# gate.net
KiCad netlist of a schematic drawn in EAGLE
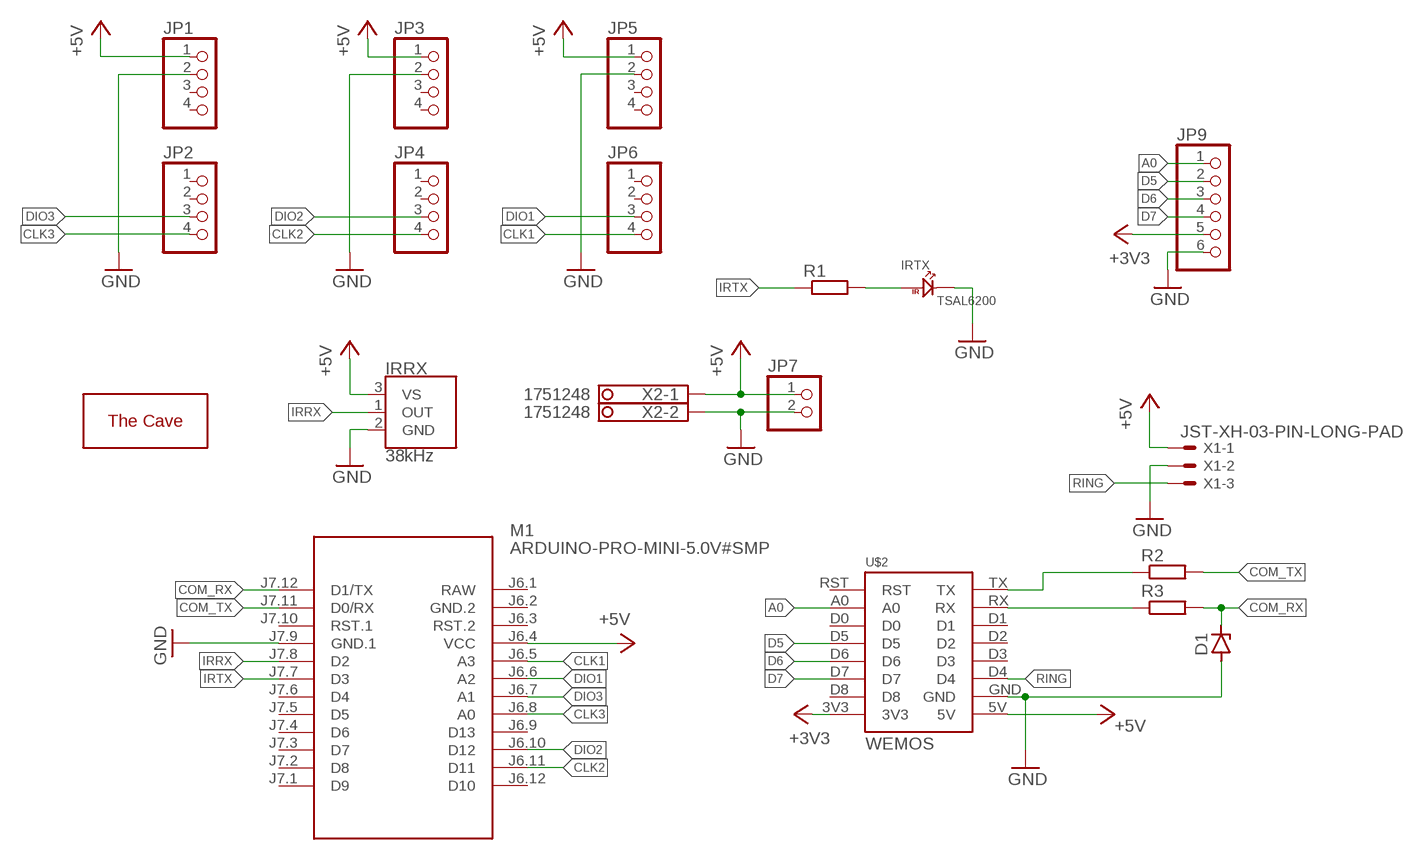
[diagram p0: schematic, sheet 1]

(export (version "E")
  (design (tool "Eeschema 10.0.6"))
  (components
    (comp (ref "D1")
      (value "ZENER-DIODEDO34-7")
      (footprint "eagle-import:DO34Z7")
      (libsource (lib "eagle-import") (part "ZENER-DIODEDO34-7"))
    )
    (comp (ref "IRRX")
      (value "38kHz")
      (footprint "eagle-import:TSOP382")
      (libsource (lib "eagle-import") (part "TSOP38238"))
    )
    (comp (ref "IRTX")
      (value "TSAL6200")
      (footprint "eagle-import:TSAL6200")
      (libsource (lib "eagle-import") (part "TSAL6200"))
    )
    (comp (ref "JP1")
      (value "PINHD-1X4")
      (footprint "eagle-import:1X04")
      (libsource (lib "eagle-import") (part "PINHD-1X4"))
    )
    (comp (ref "JP2")
      (value "PINHD-1X4")
      (footprint "eagle-import:1X04")
      (libsource (lib "eagle-import") (part "PINHD-1X4"))
    )
    (comp (ref "JP3")
      (value "PINHD-1X4")
      (footprint "eagle-import:1X04")
      (libsource (lib "eagle-import") (part "PINHD-1X4"))
    )
    (comp (ref "JP4")
      (value "PINHD-1X4")
      (footprint "eagle-import:1X04")
      (libsource (lib "eagle-import") (part "PINHD-1X4"))
    )
    (comp (ref "JP5")
      (value "PINHD-1X4")
      (footprint "eagle-import:1X04")
      (libsource (lib "eagle-import") (part "PINHD-1X4"))
    )
    (comp (ref "JP6")
      (value "PINHD-1X4")
      (footprint "eagle-import:1X04")
      (libsource (lib "eagle-import") (part "PINHD-1X4"))
    )
    (comp (ref "JP7")
      (value "PINHD-1X2")
      (footprint "eagle-import:1X02")
      (libsource (lib "eagle-import") (part "PINHD-1X2"))
    )
    (comp (ref "JP9")
      (value "PINHD-1X6")
      (footprint "eagle-import:1X06")
      (libsource (lib "eagle-import") (part "PINHD-1X6"))
    )
    (comp (ref "M1")
      (value "ARDUINO-PRO-MINI-5.0V#SMP")
      (footprint "eagle-import:ARDUINO-PRO-MINI#SMP")
      (libsource (lib "eagle-import") (part "ARDUINO-PRO-MINI-#SMP5.0V"))
    )
    (comp (ref "R1")
      (value "R-EU_0207/7")
      (footprint "eagle-import:0207_7")
      (libsource (lib "eagle-import") (part "R-EU_0207/7"))
    )
    (comp (ref "R2")
      (value "R-EU_0207/7")
      (footprint "eagle-import:0207_7")
      (libsource (lib "eagle-import") (part "R-EU_0207/7"))
    )
    (comp (ref "R3")
      (value "R-EU_0207/7")
      (footprint "eagle-import:0207_7")
      (libsource (lib "eagle-import") (part "R-EU_0207/7"))
    )
    (comp (ref "U$2")
      (value "WEMOS")
      (footprint "eagle-import:WEMOS")
      (libsource (lib "eagle-import") (part "WEMOS"))
    )
    (comp (ref "U$3")
      (value "THECAVE_LOGO_NEW_TOP")
      (footprint "eagle-import:NEW_LOGO_TOP")
      (libsource (lib "eagle-import") (part "THECAVE_LOGO_NEW_TOP"))
    )
    (comp (ref "X1")
      (value "JST-XH-03-PIN-LONG-PAD")
      (footprint "eagle-import:JST-XH-03-PACKAGE-LONG-PAD")
      (libsource (lib "eagle-import") (part "JST-XH-03-PIN-LONG-PAD"))
    )
    (comp (ref "X2")
      (value "1751248")
      (footprint "eagle-import:1751248")
      (libsource (lib "eagle-import") (part "1751248"))
    )
  )
  (nets
    (net (code "1") (name "+3V3") (class "Default")
      (node (ref "JP9") (pin "5") (pinfunction "5_5") (pintype "passive"))
      (node (ref "U$2") (pin "3V3") (pinfunction "3V3_3V3") (pintype "bidirectional"))
    )
    (net (code "2") (name "+5V") (class "Default")
      (node (ref "IRRX") (pin "3") (pinfunction "VS_3") (pintype "bidirectional"))
      (node (ref "JP1") (pin "1") (pinfunction "1_1") (pintype "passive"))
      (node (ref "JP3") (pin "1") (pinfunction "1_1") (pintype "passive"))
      (node (ref "JP5") (pin "1") (pinfunction "1_1") (pintype "passive"))
      (node (ref "JP7") (pin "1") (pinfunction "1_1") (pintype "passive"))
      (node (ref "M1") (pin "J6.4") (pinfunction "VCC_J6.4") (pintype "power_in"))
      (node (ref "U$2") (pin "5V") (pinfunction "5V_5V") (pintype "bidirectional"))
      (node (ref "X1") (pin "1") (pinfunction "S_1") (pintype "passive"))
      (node (ref "X2") (pin "1") (pinfunction "K_1") (pintype "passive"))
    )
    (net (code "3") (name "/GND.2") (class "Default")
      (node (ref "M1") (pin "J6.2") (pinfunction "GND.2_J6.2") (pintype "power_in"))
    )
    (net (code "4") (name "/RAW") (class "Default")
      (node (ref "M1") (pin "J6.1") (pinfunction "RAW_J6.1") (pintype "power_in"))
    )
    (net (code "5") (name "A0") (class "Default")
      (node (ref "JP9") (pin "1") (pinfunction "1_1") (pintype "passive"))
      (node (ref "U$2") (pin "A0") (pinfunction "A0_A0") (pintype "bidirectional"))
    )
    (net (code "6") (name "CLK1") (class "Default")
      (node (ref "JP6") (pin "4") (pinfunction "4_4") (pintype "passive"))
      (node (ref "M1") (pin "J6.5") (pinfunction "A3_J6.5") (pintype "bidirectional"))
    )
    (net (code "7") (name "CLK2") (class "Default")
      (node (ref "JP4") (pin "4") (pinfunction "4_4") (pintype "passive"))
      (node (ref "M1") (pin "J6.11") (pinfunction "D11_J6.11") (pintype "bidirectional"))
    )
    (net (code "8") (name "CLK3") (class "Default")
      (node (ref "JP2") (pin "4") (pinfunction "4_4") (pintype "passive"))
      (node (ref "M1") (pin "J6.8") (pinfunction "A0_J6.8") (pintype "bidirectional"))
    )
    (net (code "9") (name "COM_RX") (class "Default")
      (node (ref "D1") (pin "C") (pinfunction "C_C") (pintype "passive"))
      (node (ref "M1") (pin "J7.12") (pinfunction "D1/TX_J7.12") (pintype "bidirectional"))
      (node (ref "R3") (pin "2") (pinfunction "2_2") (pintype "passive"))
    )
    (net (code "10") (name "COM_TX") (class "Default")
      (node (ref "M1") (pin "J7.11") (pinfunction "D0/RX_J7.11") (pintype "bidirectional"))
      (node (ref "R2") (pin "2") (pinfunction "2_2") (pintype "passive"))
    )
    (net (code "11") (name "D5") (class "Default")
      (node (ref "JP9") (pin "2") (pinfunction "2_2") (pintype "passive"))
      (node (ref "U$2") (pin "D5") (pinfunction "D5_D5") (pintype "bidirectional"))
    )
    (net (code "12") (name "D6") (class "Default")
      (node (ref "JP9") (pin "3") (pinfunction "3_3") (pintype "passive"))
      (node (ref "U$2") (pin "D6") (pinfunction "D6_D6") (pintype "bidirectional"))
    )
    (net (code "13") (name "D7") (class "Default")
      (node (ref "JP9") (pin "4") (pinfunction "4_4") (pintype "passive"))
      (node (ref "U$2") (pin "D7") (pinfunction "D7_D7") (pintype "bidirectional"))
    )
    (net (code "14") (name "DIO1") (class "Default")
      (node (ref "JP6") (pin "3") (pinfunction "3_3") (pintype "passive"))
      (node (ref "M1") (pin "J6.6") (pinfunction "A2_J6.6") (pintype "bidirectional"))
    )
    (net (code "15") (name "DIO2") (class "Default")
      (node (ref "JP4") (pin "3") (pinfunction "3_3") (pintype "passive"))
      (node (ref "M1") (pin "J6.10") (pinfunction "D12_J6.10") (pintype "bidirectional"))
    )
    (net (code "16") (name "DIO3") (class "Default")
      (node (ref "JP2") (pin "3") (pinfunction "3_3") (pintype "passive"))
      (node (ref "M1") (pin "J6.7") (pinfunction "A1_J6.7") (pintype "bidirectional"))
    )
    (net (code "17") (name "GND") (class "Default")
      (node (ref "D1") (pin "A") (pinfunction "A_A") (pintype "passive"))
      (node (ref "IRRX") (pin "2") (pinfunction "GND_2") (pintype "bidirectional"))
      (node (ref "IRTX") (pin "N") (pinfunction "N_N") (pintype "bidirectional"))
      (node (ref "JP1") (pin "2") (pinfunction "2_2") (pintype "passive"))
      (node (ref "JP3") (pin "2") (pinfunction "2_2") (pintype "passive"))
      (node (ref "JP5") (pin "2") (pinfunction "2_2") (pintype "passive"))
      (node (ref "JP7") (pin "2") (pinfunction "2_2") (pintype "passive"))
      (node (ref "JP9") (pin "6") (pinfunction "6_6") (pintype "passive"))
      (node (ref "M1") (pin "J7.9") (pinfunction "GND.1_J7.9") (pintype "power_in"))
      (node (ref "U$2") (pin "GND") (pinfunction "GND_GND") (pintype "bidirectional"))
      (node (ref "X1") (pin "2") (pinfunction "S_2") (pintype "passive"))
      (node (ref "X2") (pin "2") (pinfunction "K_2") (pintype "passive"))
    )
    (net (code "18") (name "IRRX") (class "Default")
      (node (ref "IRRX") (pin "1") (pinfunction "OUT_1") (pintype "bidirectional"))
      (node (ref "M1") (pin "J7.8") (pinfunction "D2_J7.8") (pintype "bidirectional"))
    )
    (net (code "19") (name "IRTX") (class "Default")
      (node (ref "M1") (pin "J7.7") (pinfunction "D3_J7.7") (pintype "bidirectional"))
      (node (ref "R1") (pin "1") (pinfunction "1_1") (pintype "passive"))
    )
    (net (code "20") (name "Net-(IRTX-PadP)") (class "Default")
      (node (ref "IRTX") (pin "P") (pinfunction "P_P") (pintype "bidirectional"))
      (node (ref "R1") (pin "2") (pinfunction "2_2") (pintype "passive"))
    )
    (net (code "21") (name "Net-(R2-Pad1)") (class "Default")
      (node (ref "R2") (pin "1") (pinfunction "1_1") (pintype "passive"))
      (node (ref "U$2") (pin "TX") (pinfunction "TX_TX") (pintype "bidirectional"))
    )
    (net (code "22") (name "Net-(R3-Pad1)") (class "Default")
      (node (ref "R3") (pin "1") (pinfunction "1_1") (pintype "passive"))
      (node (ref "U$2") (pin "RX") (pinfunction "RX_RX") (pintype "bidirectional"))
    )
    (net (code "23") (name "RING") (class "Default")
      (node (ref "U$2") (pin "D4") (pinfunction "D4_D4") (pintype "bidirectional"))
      (node (ref "X1") (pin "3") (pinfunction "S_3") (pintype "passive"))
    )
    (net (code "24") (name "unconnected-(JP1-Pad3)") (class "Default")
      (node (ref "JP1") (pin "3") (pinfunction "3_3") (pintype "passive"))
    )
    (net (code "25") (name "unconnected-(JP1-Pad4)") (class "Default")
      (node (ref "JP1") (pin "4") (pinfunction "4_4") (pintype "passive"))
    )
    (net (code "26") (name "unconnected-(JP2-Pad1)") (class "Default")
      (node (ref "JP2") (pin "1") (pinfunction "1_1") (pintype "passive"))
    )
    (net (code "27") (name "unconnected-(JP2-Pad2)") (class "Default")
      (node (ref "JP2") (pin "2") (pinfunction "2_2") (pintype "passive"))
    )
    (net (code "28") (name "unconnected-(JP3-Pad3)") (class "Default")
      (node (ref "JP3") (pin "3") (pinfunction "3_3") (pintype "passive"))
    )
    (net (code "29") (name "unconnected-(JP3-Pad4)") (class "Default")
      (node (ref "JP3") (pin "4") (pinfunction "4_4") (pintype "passive"))
    )
    (net (code "30") (name "unconnected-(JP4-Pad1)") (class "Default")
      (node (ref "JP4") (pin "1") (pinfunction "1_1") (pintype "passive"))
    )
    (net (code "31") (name "unconnected-(JP4-Pad2)") (class "Default")
      (node (ref "JP4") (pin "2") (pinfunction "2_2") (pintype "passive"))
    )
    (net (code "32") (name "unconnected-(JP5-Pad3)") (class "Default")
      (node (ref "JP5") (pin "3") (pinfunction "3_3") (pintype "passive"))
    )
    (net (code "33") (name "unconnected-(JP5-Pad4)") (class "Default")
      (node (ref "JP5") (pin "4") (pinfunction "4_4") (pintype "passive"))
    )
    (net (code "34") (name "unconnected-(JP6-Pad1)") (class "Default")
      (node (ref "JP6") (pin "1") (pinfunction "1_1") (pintype "passive"))
    )
    (net (code "35") (name "unconnected-(JP6-Pad2)") (class "Default")
      (node (ref "JP6") (pin "2") (pinfunction "2_2") (pintype "passive"))
    )
    (net (code "36") (name "unconnected-(M1-D4-PadJ7.6)") (class "Default")
      (node (ref "M1") (pin "J7.6") (pinfunction "D4_J7.6") (pintype "bidirectional"))
    )
    (net (code "37") (name "unconnected-(M1-D5-PadJ7.5)") (class "Default")
      (node (ref "M1") (pin "J7.5") (pinfunction "D5_J7.5") (pintype "bidirectional"))
    )
    (net (code "38") (name "unconnected-(M1-D6-PadJ7.4)") (class "Default")
      (node (ref "M1") (pin "J7.4") (pinfunction "D6_J7.4") (pintype "bidirectional"))
    )
    (net (code "39") (name "unconnected-(M1-D7-PadJ7.3)") (class "Default")
      (node (ref "M1") (pin "J7.3") (pinfunction "D7_J7.3") (pintype "bidirectional"))
    )
    (net (code "40") (name "unconnected-(M1-D8-PadJ7.2)") (class "Default")
      (node (ref "M1") (pin "J7.2") (pinfunction "D8_J7.2") (pintype "bidirectional"))
    )
    (net (code "41") (name "unconnected-(M1-D9-PadJ7.1)") (class "Default")
      (node (ref "M1") (pin "J7.1") (pinfunction "D9_J7.1") (pintype "bidirectional"))
    )
    (net (code "42") (name "unconnected-(M1-D10-PadJ6.12)") (class "Default")
      (node (ref "M1") (pin "J6.12") (pinfunction "D10_J6.12") (pintype "bidirectional"))
    )
    (net (code "43") (name "unconnected-(M1-D13-PadJ6.9)") (class "Default")
      (node (ref "M1") (pin "J6.9") (pinfunction "D13_J6.9") (pintype "bidirectional"))
    )
    (net (code "44") (name "unconnected-(M1-RST.1-PadJ7.10)") (class "Default")
      (node (ref "M1") (pin "J7.10") (pinfunction "RST.1_J7.10") (pintype "bidirectional"))
    )
    (net (code "45") (name "unconnected-(M1-RST.2-PadJ6.3)") (class "Default")
      (node (ref "M1") (pin "J6.3") (pinfunction "RST.2_J6.3") (pintype "bidirectional"))
    )
    (net (code "46") (name "unconnected-(U$2-PadD0)") (class "Default")
      (node (ref "U$2") (pin "D0") (pinfunction "D0_D0") (pintype "bidirectional"))
    )
    (net (code "47") (name "unconnected-(U$2-PadD1)") (class "Default")
      (node (ref "U$2") (pin "D1") (pinfunction "D1_D1") (pintype "bidirectional"))
    )
    (net (code "48") (name "unconnected-(U$2-PadD2)") (class "Default")
      (node (ref "U$2") (pin "D2") (pinfunction "D2_D2") (pintype "bidirectional"))
    )
    (net (code "49") (name "unconnected-(U$2-PadD3)") (class "Default")
      (node (ref "U$2") (pin "D3") (pinfunction "D3_D3") (pintype "bidirectional"))
    )
    (net (code "50") (name "unconnected-(U$2-PadD8)") (class "Default")
      (node (ref "U$2") (pin "D8") (pinfunction "D8_D8") (pintype "bidirectional"))
    )
    (net (code "51") (name "unconnected-(U$2-PadRST)") (class "Default")
      (node (ref "U$2") (pin "RST") (pinfunction "RST_RST") (pintype "bidirectional"))
    )
  )
)
